# Temp_In.net
KiCad netlist of a schematic drawn in Altium Designer
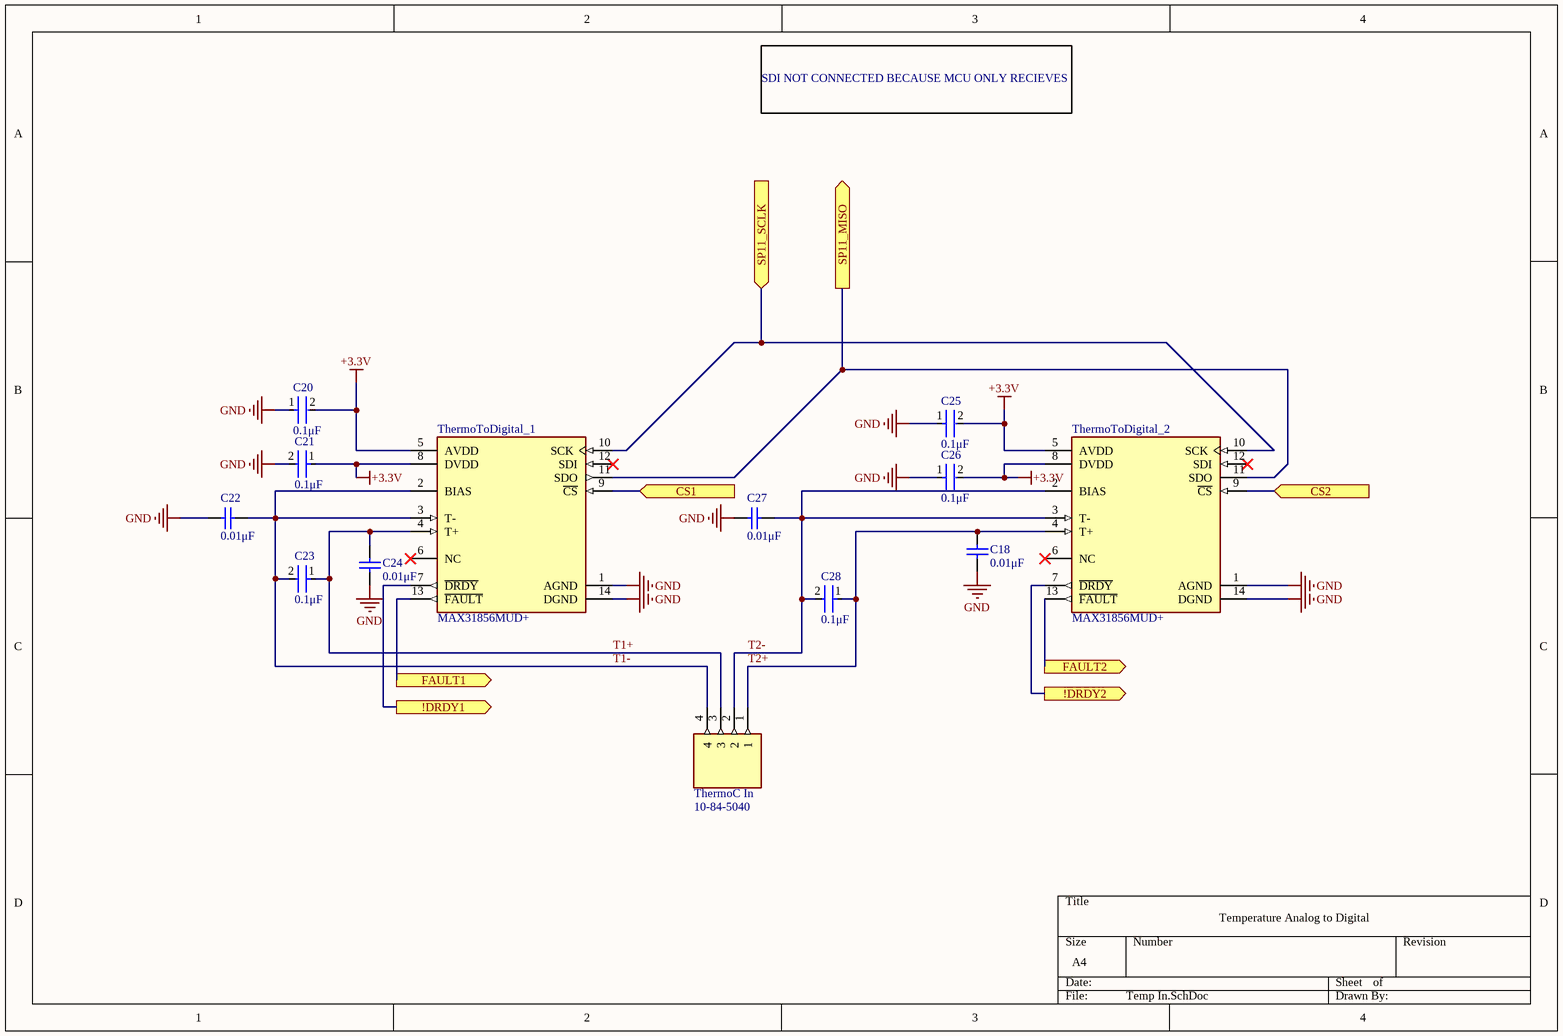
[diagram p0: Temp In.SchDoc]

(export (version "E")
  (design (tool "Eeschema 10.0.6"))
  (components
    (comp (ref "C18")
      (value "0.01μF")
      (footprint "CAPC1608X90X35ML10T15")
      (description "Chip Capacitor, 10 nF, +/- 10%, 50 V, -55 to 125 degC, 0603 (1608 Metric), RoHS, Tape and Reel")
      (fields (field (name "VOLTAGE") "50V") (field (name "TOLERANCE") "10%"))
      (libsource (lib "Altium Content Vault") (part "CAP-NP-2"))
    )
    (comp (ref "C20")
      (value "0.1μF")
      (footprint "FP-C0603C-CF-MFG")
      (description "CAP CER 0.1UF 50V X7R 0603")
      (fields (field (name "TOLERANCE") "0.1") (field (name "MANUFACTURER") "KEMET"))
      (libsource (lib "Altium Content Vault") (part "b4654b650e69147ec39a6b967a45e02"))
    )
    (comp (ref "C21")
      (value "0.1μF")
      (footprint "FP-C0603C-CF-MFG")
      (description "CAP CER 0.1UF 50V X7R 0603")
      (fields (field (name "TOLERANCE") "0.1") (field (name "MANUFACTURER") "KEMET"))
      (libsource (lib "Altium Content Vault") (part "b4654b650e69147ec39a6b967a45e02"))
    )
    (comp (ref "C22")
      (value "0.01μF")
      (footprint "CAPC1608X90X35ML10T15")
      (description "Chip Capacitor, 10 nF, +/- 10%, 50 V, -55 to 125 degC, 0603 (1608 Metric), RoHS, Tape and Reel")
      (fields (field (name "VOLTAGE") "50V") (field (name "TOLERANCE") "10%"))
      (libsource (lib "Altium Content Vault") (part "CAP-NP-2"))
    )
    (comp (ref "C23")
      (value "0.1μF")
      (footprint "FP-C0603C-CF-MFG")
      (description "CAP CER 0.1UF 50V X7R 0603")
      (fields (field (name "TOLERANCE") "0.1") (field (name "MANUFACTURER") "KEMET"))
      (libsource (lib "Altium Content Vault") (part "b4654b650e69147ec39a6b967a45e02"))
    )
    (comp (ref "C24")
      (value "0.01μF")
      (footprint "CAPC1608X90X35ML10T15")
      (description "Chip Capacitor, 10 nF, +/- 10%, 50 V, -55 to 125 degC, 0603 (1608 Metric), RoHS, Tape and Reel")
      (fields (field (name "VOLTAGE") "50V") (field (name "TOLERANCE") "10%"))
      (libsource (lib "Altium Content Vault") (part "CAP-NP-2"))
    )
    (comp (ref "C25")
      (value "0.1μF")
      (footprint "FP-C0603C-CF-MFG")
      (description "CAP CER 0.1UF 50V X7R 0603")
      (fields (field (name "TOLERANCE") "0.1") (field (name "MANUFACTURER") "KEMET"))
      (libsource (lib "Altium Content Vault") (part "b4654b650e69147ec39a6b967a45e02"))
    )
    (comp (ref "C26")
      (value "0.1μF")
      (footprint "FP-C0603C-CF-MFG")
      (description "CAP CER 0.1UF 50V X7R 0603")
      (fields (field (name "TOLERANCE") "0.1") (field (name "MANUFACTURER") "KEMET"))
      (libsource (lib "Altium Content Vault") (part "b4654b650e69147ec39a6b967a45e02"))
    )
    (comp (ref "C27")
      (value "0.01μF")
      (footprint "CAPC1608X90X35ML10T15")
      (description "Chip Capacitor, 10 nF, +/- 10%, 50 V, -55 to 125 degC, 0603 (1608 Metric), RoHS, Tape and Reel")
      (fields (field (name "VOLTAGE") "50V") (field (name "TOLERANCE") "10%"))
      (libsource (lib "Altium Content Vault") (part "CAP-NP-2"))
    )
    (comp (ref "C28")
      (value "0.1μF")
      (footprint "FP-C0603C-CF-MFG")
      (description "CAP CER 0.1UF 50V X7R 0603")
      (fields (field (name "TOLERANCE") "0.1") (field (name "MANUFACTURER") "KEMET"))
      (libsource (lib "Altium Content Vault") (part "b4654b650e69147ec39a6b967a45e02"))
    )
    (comp (ref "ThermoC In")
      (value "10-84-5040")
      (footprint "SamacSys:10845040")
      (description "Connector")
      (libsource (lib "*") (part "10-84-5040"))
    )
    (comp (ref "ThermoToDigital_1")
      (value "MAX31856MUD+")
      (footprint "FP-U14-2-MFG")
      (description "IC CONV THERMOCOUPLE 14TSSOP")
      (libsource (lib "Altium Content Vault") (part "746ee3d58a922cadd982a8de1b076a0"))
    )
    (comp (ref "ThermoToDigital_2")
      (value "MAX31856MUD+")
      (footprint "FP-U14-2-MFG")
      (description "IC CONV THERMOCOUPLE 14TSSOP")
      (libsource (lib "Altium Content Vault") (part "746ee3d58a922cadd982a8de1b076a0"))
    )
  )
  (nets
    (net (code "1") (name "+3.3V") (class "Default")
      (node (ref "C20") (pin "2") (pinfunction "2_2") (pintype "passive"))
      (node (ref "C21") (pin "1") (pinfunction "1_1") (pintype "passive"))
      (node (ref "C25") (pin "2") (pinfunction "2_2") (pintype "passive"))
      (node (ref "C26") (pin "2") (pinfunction "2_2") (pintype "passive"))
      (node (ref "ThermoToDigital_1") (pin "5") (pinfunction "AVDD_5") (pintype "power_in"))
      (node (ref "ThermoToDigital_1") (pin "8") (pinfunction "DVDD_8") (pintype "power_in"))
      (node (ref "ThermoToDigital_2") (pin "5") (pinfunction "AVDD_5") (pintype "power_in"))
      (node (ref "ThermoToDigital_2") (pin "8") (pinfunction "DVDD_8") (pintype "power_in"))
    )
    (net (code "2") (name "/!DRDY1") (class "Default")
      (node (ref "ThermoToDigital_1") (pin "7") (pinfunction "~{DRDY}_7") (pintype "output"))
    )
    (net (code "3") (name "/!DRDY2") (class "Default")
      (node (ref "ThermoToDigital_2") (pin "7") (pinfunction "~{DRDY}_7") (pintype "output"))
    )
    (net (code "4") (name "/CS1") (class "Default")
      (node (ref "ThermoToDigital_1") (pin "9") (pinfunction "~{CS}_9") (pintype "input"))
    )
    (net (code "5") (name "/CS2") (class "Default")
      (node (ref "ThermoToDigital_2") (pin "9") (pinfunction "~{CS}_9") (pintype "input"))
    )
    (net (code "6") (name "/FAULT1") (class "Default")
      (node (ref "ThermoToDigital_1") (pin "13") (pinfunction "~{FAULT}_13") (pintype "output"))
    )
    (net (code "7") (name "/FAULT2") (class "Default")
      (node (ref "ThermoToDigital_2") (pin "13") (pinfunction "~{FAULT}_13") (pintype "output"))
    )
    (net (code "8") (name "/SP11_MISO") (class "Default")
      (node (ref "ThermoToDigital_1") (pin "11") (pinfunction "SDO_11") (pintype "passive"))
      (node (ref "ThermoToDigital_2") (pin "11") (pinfunction "SDO_11") (pintype "passive"))
    )
    (net (code "9") (name "/SP11_SCLK") (class "Default")
      (node (ref "ThermoToDigital_1") (pin "10") (pinfunction "SCK_10") (pintype "input"))
      (node (ref "ThermoToDigital_2") (pin "10") (pinfunction "SCK_10") (pintype "input"))
    )
    (net (code "10") (name "/T1+") (class "Default")
      (node (ref "C23") (pin "1") (pinfunction "1_1") (pintype "passive"))
      (node (ref "C24") (pin "2") (pinfunction "2_2") (pintype "passive"))
      (node (ref "ThermoC In") (pin "3") (pinfunction "3_3") (pintype "output"))
      (node (ref "ThermoToDigital_1") (pin "4") (pinfunction "T+_4") (pintype "input"))
    )
    (net (code "11") (name "/T1-") (class "Default")
      (node (ref "C22") (pin "1") (pinfunction "1_1") (pintype "passive"))
      (node (ref "C23") (pin "2") (pinfunction "2_2") (pintype "passive"))
      (node (ref "ThermoC In") (pin "4") (pinfunction "4_4") (pintype "output"))
      (node (ref "ThermoToDigital_1") (pin "2") (pinfunction "BIAS_2") (pintype "passive"))
      (node (ref "ThermoToDigital_1") (pin "3") (pinfunction "T-_3") (pintype "input"))
    )
    (net (code "12") (name "/T2+") (class "Default")
      (node (ref "C18") (pin "2") (pinfunction "2_2") (pintype "passive"))
      (node (ref "C28") (pin "1") (pinfunction "1_1") (pintype "passive"))
      (node (ref "ThermoC In") (pin "1") (pinfunction "1_1") (pintype "output"))
      (node (ref "ThermoToDigital_2") (pin "4") (pinfunction "T+_4") (pintype "input"))
    )
    (net (code "13") (name "/T2-") (class "Default")
      (node (ref "C27") (pin "1") (pinfunction "1_1") (pintype "passive"))
      (node (ref "C28") (pin "2") (pinfunction "2_2") (pintype "passive"))
      (node (ref "ThermoC In") (pin "2") (pinfunction "2_2") (pintype "output"))
      (node (ref "ThermoToDigital_2") (pin "2") (pinfunction "BIAS_2") (pintype "passive"))
      (node (ref "ThermoToDigital_2") (pin "3") (pinfunction "T-_3") (pintype "input"))
    )
    (net (code "14") (name "GND") (class "Default")
      (node (ref "C18") (pin "1") (pinfunction "1_1") (pintype "passive"))
      (node (ref "C20") (pin "1") (pinfunction "1_1") (pintype "passive"))
      (node (ref "C21") (pin "2") (pinfunction "2_2") (pintype "passive"))
      (node (ref "C22") (pin "2") (pinfunction "2_2") (pintype "passive"))
      (node (ref "C24") (pin "1") (pinfunction "1_1") (pintype "passive"))
      (node (ref "C25") (pin "1") (pinfunction "1_1") (pintype "passive"))
      (node (ref "C26") (pin "1") (pinfunction "1_1") (pintype "passive"))
      (node (ref "C27") (pin "2") (pinfunction "2_2") (pintype "passive"))
      (node (ref "ThermoToDigital_1") (pin "1") (pinfunction "AGND_1") (pintype "power_in"))
      (node (ref "ThermoToDigital_1") (pin "14") (pinfunction "DGND_14") (pintype "power_in"))
      (node (ref "ThermoToDigital_2") (pin "1") (pinfunction "AGND_1") (pintype "power_in"))
      (node (ref "ThermoToDigital_2") (pin "14") (pinfunction "DGND_14") (pintype "power_in"))
    )
    (net (code "15") (name "unconnected-(ThermoToDigital_1-NC-Pad6)") (class "Default")
      (node (ref "ThermoToDigital_1") (pin "6") (pinfunction "NC_6") (pintype "passive+no_connect"))
    )
    (net (code "16") (name "unconnected-(ThermoToDigital_1-SDI-Pad12)") (class "Default")
      (node (ref "ThermoToDigital_1") (pin "12") (pinfunction "SDI_12") (pintype "input+no_connect"))
    )
    (net (code "17") (name "unconnected-(ThermoToDigital_2-NC-Pad6)") (class "Default")
      (node (ref "ThermoToDigital_2") (pin "6") (pinfunction "NC_6") (pintype "passive+no_connect"))
    )
    (net (code "18") (name "unconnected-(ThermoToDigital_2-SDI-Pad12)") (class "Default")
      (node (ref "ThermoToDigital_2") (pin "12") (pinfunction "SDI_12") (pintype "input+no_connect"))
    )
  )
)
